# OSO-MISC-20-011_Capacitive_Soil_Moisture.net
KiCad netlist of a schematic drawn in EAGLE
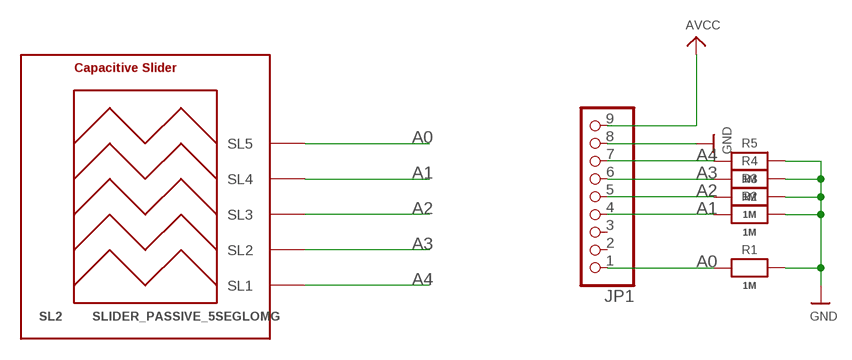
[diagram p0: schematic, sheet 1]

(export (version "E")
  (design (tool "Eeschema 10.0.6"))
  (components
    (comp (ref "JP1")
      (value "HEADER-1X9_JSTSH")
      (footprint "eagle-import:JST_SH9")
      (libsource (lib "eagle-import") (part "HEADER-1X9_JSTSH"))
    )
    (comp (ref "R1")
      (value "1M")
      (footprint "eagle-import:0603-NO")
      (libsource (lib "eagle-import") (part "RESISTOR_0603_NOOUT"))
    )
    (comp (ref "R2")
      (value "1M")
      (footprint "eagle-import:0603-NO")
      (libsource (lib "eagle-import") (part "RESISTOR_0603_NOOUT"))
    )
    (comp (ref "R3")
      (value "1M")
      (footprint "eagle-import:0603-NO")
      (libsource (lib "eagle-import") (part "RESISTOR_0603_NOOUT"))
    )
    (comp (ref "R4")
      (value "1M")
      (footprint "eagle-import:0603-NO")
      (libsource (lib "eagle-import") (part "RESISTOR_0603_NOOUT"))
    )
    (comp (ref "R5")
      (value "1M")
      (footprint "eagle-import:0603-NO")
      (libsource (lib "eagle-import") (part "RESISTOR_0603_NOOUT"))
    )
    (comp (ref "SL2")
      (value "SLIDER_PASSIVE_5SEGLOMG")
      (footprint "eagle-import:SLIDER_PASSIVE_5SEG_12MM_LOMG")
      (libsource (lib "eagle-import") (part "SLIDER_PASSIVE_5SEGLOMG"))
    )
  )
  (nets
    (net (code "1") (name "/A0") (class "Default")
      (node (ref "JP1") (pin "1") (pinfunction "1_1") (pintype "passive"))
      (node (ref "R1") (pin "1") (pinfunction "1_1") (pintype "passive"))
      (node (ref "SL2") (pin "SL5") (pinfunction "SL5_SL5") (pintype "passive"))
    )
    (net (code "2") (name "/A1") (class "Default")
      (node (ref "JP1") (pin "4") (pinfunction "4_4") (pintype "passive"))
      (node (ref "R2") (pin "1") (pinfunction "1_1") (pintype "passive"))
      (node (ref "SL2") (pin "SL4") (pinfunction "SL4_SL4") (pintype "passive"))
    )
    (net (code "3") (name "/A2") (class "Default")
      (node (ref "JP1") (pin "5") (pinfunction "5_5") (pintype "passive"))
      (node (ref "R3") (pin "1") (pinfunction "1_1") (pintype "passive"))
      (node (ref "SL2") (pin "SL3") (pinfunction "SL3_SL3") (pintype "passive"))
    )
    (net (code "4") (name "/A3") (class "Default")
      (node (ref "JP1") (pin "6") (pinfunction "6_6") (pintype "passive"))
      (node (ref "R4") (pin "1") (pinfunction "1_1") (pintype "passive"))
      (node (ref "SL2") (pin "SL2") (pinfunction "SL2_SL2") (pintype "passive"))
    )
    (net (code "5") (name "/A4") (class "Default")
      (node (ref "JP1") (pin "7") (pinfunction "7_7") (pintype "passive"))
      (node (ref "R5") (pin "1") (pinfunction "1_1") (pintype "passive"))
      (node (ref "SL2") (pin "SL1") (pinfunction "SL1_SL1") (pintype "passive"))
    )
    (net (code "6") (name "AVCC") (class "Default")
      (node (ref "JP1") (pin "9") (pinfunction "9_9") (pintype "passive"))
    )
    (net (code "7") (name "GND") (class "Default")
      (node (ref "JP1") (pin "8") (pinfunction "8_8") (pintype "passive"))
      (node (ref "R1") (pin "2") (pinfunction "2_2") (pintype "passive"))
      (node (ref "R2") (pin "2") (pinfunction "2_2") (pintype "passive"))
      (node (ref "R3") (pin "2") (pinfunction "2_2") (pintype "passive"))
      (node (ref "R4") (pin "2") (pinfunction "2_2") (pintype "passive"))
      (node (ref "R5") (pin "2") (pinfunction "2_2") (pintype "passive"))
    )
    (net (code "8") (name "unconnected-(JP1-Pad2)") (class "Default")
      (node (ref "JP1") (pin "2") (pinfunction "2_2") (pintype "passive"))
    )
    (net (code "9") (name "unconnected-(JP1-Pad3)") (class "Default")
      (node (ref "JP1") (pin "3") (pinfunction "3_3") (pintype "passive"))
    )
  )
)
